# AliDualVar_B.net
KiCad netlist of a schematic drawn in EAGLE
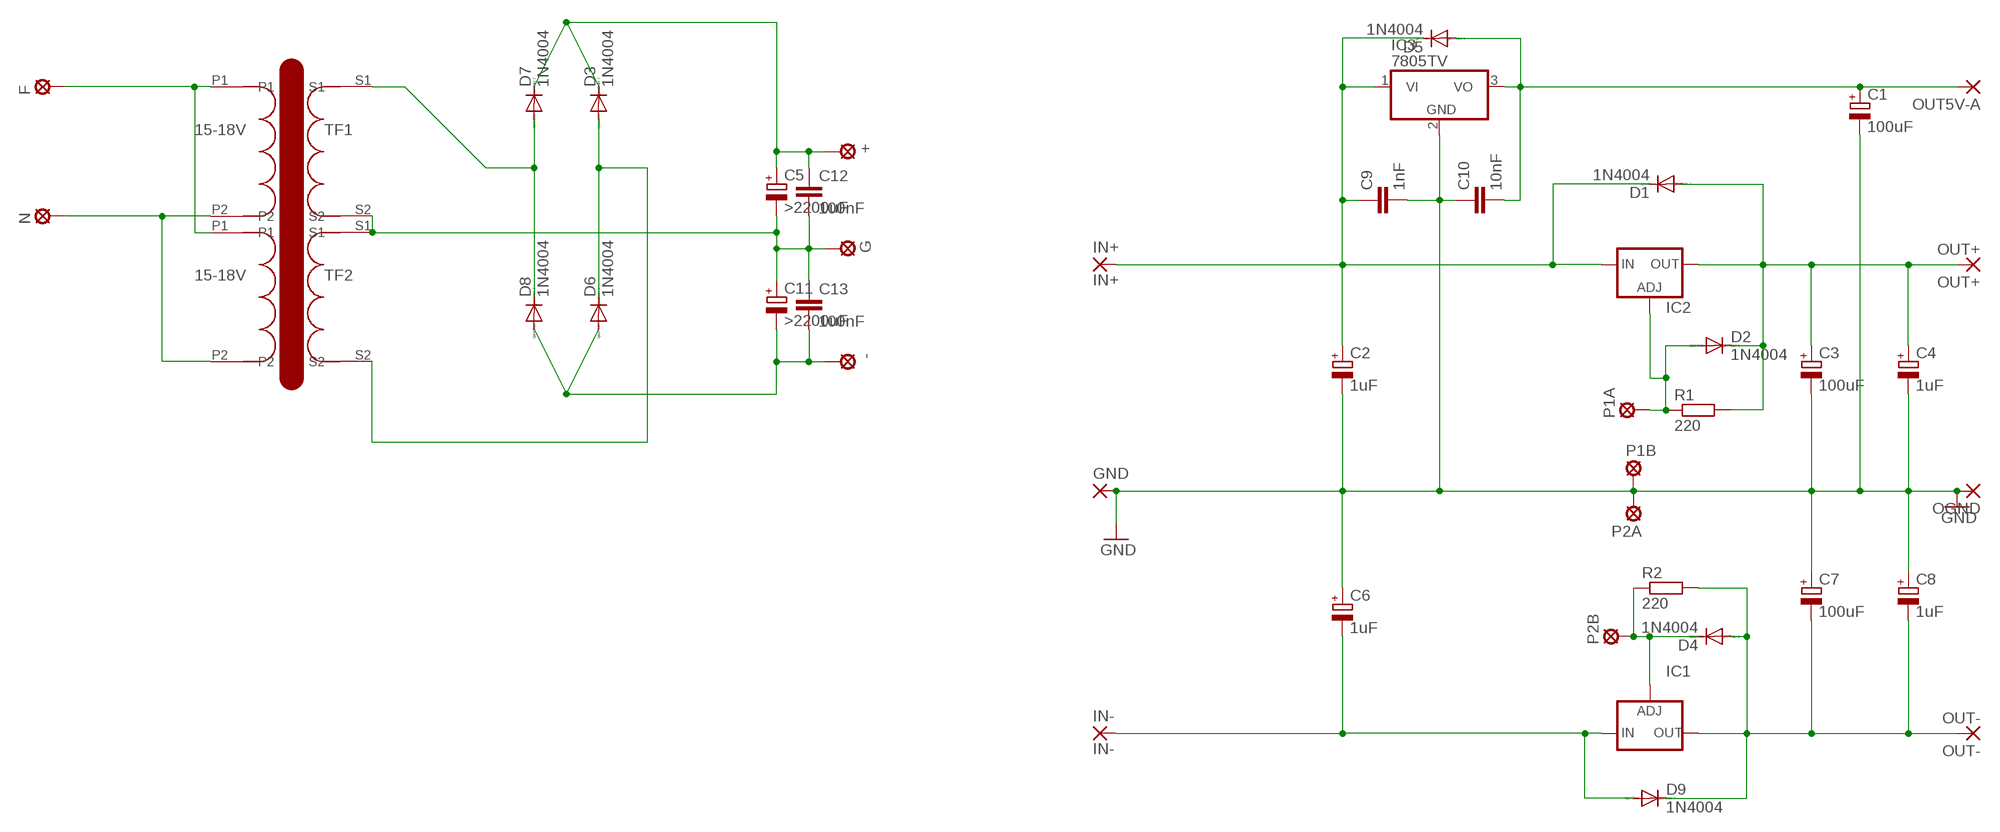
[diagram p0: schematic, sheet 1]

(export (version "E")
  (design (tool "Eeschema 10.0.6"))
  (components
    (comp (ref "+")
      (value "LSP10")
      (footprint "eagle-import:LSP10")
      (libsource (lib "eagle-import") (part "LSP10"))
    )
    (comp (ref "-")
      (value "LSP10")
      (footprint "eagle-import:LSP10")
      (libsource (lib "eagle-import") (part "LSP10"))
    )
    (comp (ref "C1")
      (value "100uF")
      (footprint "eagle-import:E5-13")
      (libsource (lib "eagle-import") (part "CPOL-EUE5-13"))
    )
    (comp (ref "C2")
      (value "1uF")
      (footprint "eagle-import:E5-13")
      (libsource (lib "eagle-import") (part "CPOL-EUE5-13"))
    )
    (comp (ref "C3")
      (value "100uF")
      (footprint "eagle-import:E5-13")
      (libsource (lib "eagle-import") (part "CPOL-EUE5-13"))
    )
    (comp (ref "C4")
      (value "1uF")
      (footprint "eagle-import:E5-13")
      (libsource (lib "eagle-import") (part "CPOL-EUE5-13"))
    )
    (comp (ref "C5")
      (value ">2200uF")
      (footprint "eagle-import:E7,5-16")
      (libsource (lib "eagle-import") (part "CPOL-EUE7.5-16"))
    )
    (comp (ref "C6")
      (value "1uF")
      (footprint "eagle-import:E5-13")
      (libsource (lib "eagle-import") (part "CPOL-EUE5-13"))
    )
    (comp (ref "C7")
      (value "100uF")
      (footprint "eagle-import:E5-13")
      (libsource (lib "eagle-import") (part "CPOL-EUE5-13"))
    )
    (comp (ref "C8")
      (value "1uF")
      (footprint "eagle-import:E5-13")
      (libsource (lib "eagle-import") (part "CPOL-EUE5-13"))
    )
    (comp (ref "C9")
      (value "1nF")
      (footprint "eagle-import:C025-024X044")
      (libsource (lib "eagle-import") (part "C-EU025-024X044"))
    )
    (comp (ref "C10")
      (value "10nF")
      (footprint "eagle-import:C025-024X044")
      (libsource (lib "eagle-import") (part "C-EU025-024X044"))
    )
    (comp (ref "C11")
      (value ">2200uF")
      (footprint "eagle-import:E7,5-16")
      (libsource (lib "eagle-import") (part "CPOL-EUE7.5-16"))
    )
    (comp (ref "C12")
      (value "100nF")
      (footprint "eagle-import:C050-035X075")
      (libsource (lib "eagle-import") (part "resistor_C-EU050-035X075"))
    )
    (comp (ref "C13")
      (value "100nF")
      (footprint "eagle-import:C050-035X075")
      (libsource (lib "eagle-import") (part "resistor_C-EU050-035X075"))
    )
    (comp (ref "D1")
      (value "1N4004")
      (footprint "eagle-import:DO41-10")
      (libsource (lib "eagle-import") (part "1N4004"))
    )
    (comp (ref "D2")
      (value "1N4004")
      (footprint "eagle-import:DO41-10")
      (libsource (lib "eagle-import") (part "1N4004"))
    )
    (comp (ref "D3")
      (value "1N4004")
      (footprint "eagle-import:DO41-10")
      (libsource (lib "eagle-import") (part "1N4004"))
    )
    (comp (ref "D4")
      (value "1N4004")
      (footprint "eagle-import:DO41-10")
      (libsource (lib "eagle-import") (part "1N4004"))
    )
    (comp (ref "D5")
      (value "1N4004")
      (footprint "eagle-import:DO41-10")
      (libsource (lib "eagle-import") (part "1N4004"))
    )
    (comp (ref "D6")
      (value "1N4004")
      (footprint "eagle-import:DO41-10")
      (libsource (lib "eagle-import") (part "1N4004"))
    )
    (comp (ref "D7")
      (value "1N4004")
      (footprint "eagle-import:DO41-10")
      (libsource (lib "eagle-import") (part "1N4004"))
    )
    (comp (ref "D8")
      (value "1N4004")
      (footprint "eagle-import:DO41-10")
      (libsource (lib "eagle-import") (part "1N4004"))
    )
    (comp (ref "D9")
      (value "1N4004")
      (footprint "eagle-import:DO41-10")
      (libsource (lib "eagle-import") (part "1N4004"))
    )
    (comp (ref "F")
      (value "LSP10")
      (footprint "eagle-import:LSP10")
      (libsource (lib "eagle-import") (part "LSP10"))
    )
    (comp (ref "G")
      (value "LSP10")
      (footprint "eagle-import:LSP10")
      (libsource (lib "eagle-import") (part "LSP10"))
    )
    (comp (ref "GND")
      (value "3,81/1,4")
      (footprint "eagle-import:3,81_1,4")
      (libsource (lib "eagle-import") (part "3,81/1,4"))
    )
    (comp (ref "IC1")
      (value "LM337TS")
      (footprint "eagle-import:337TS")
      (libsource (lib "eagle-import") (part "LM337TS"))
    )
    (comp (ref "IC2")
      (value "LM317TS")
      (footprint "eagle-import:317TS")
      (libsource (lib "eagle-import") (part "LM317TS"))
    )
    (comp (ref "IC3")
      (value "7805TV")
      (footprint "eagle-import:TO220V")
      (libsource (lib "eagle-import") (part "78TV05"))
    )
    (comp (ref "IN+")
      (value "IN+")
      (footprint "eagle-import:3,81_1,4")
      (libsource (lib "eagle-import") (part "3,81/1,4"))
    )
    (comp (ref "IN-")
      (value "IN-")
      (footprint "eagle-import:3,81_1,4")
      (libsource (lib "eagle-import") (part "3,81/1,4"))
    )
    (comp (ref "N")
      (value "LSP10")
      (footprint "eagle-import:LSP10")
      (libsource (lib "eagle-import") (part "LSP10"))
    )
    (comp (ref "OGND")
      (value "3,81/1,4")
      (footprint "eagle-import:3,81_1,4")
      (libsource (lib "eagle-import") (part "3,81/1,4"))
    )
    (comp (ref "OUT+")
      (value "OUT+")
      (footprint "eagle-import:3,81_1,4")
      (libsource (lib "eagle-import") (part "3,81/1,4"))
    )
    (comp (ref "OUT-")
      (value "OUT-")
      (footprint "eagle-import:3,81_1,4")
      (libsource (lib "eagle-import") (part "3,81/1,4"))
    )
    (comp (ref "OUT5V-A")
      (value "3,81/1,4")
      (footprint "eagle-import:3,81_1,4")
      (libsource (lib "eagle-import") (part "3,81/1,4"))
    )
    (comp (ref "P1A")
      (value "LSP10")
      (footprint "eagle-import:LSP10")
      (libsource (lib "eagle-import") (part "LSP10"))
    )
    (comp (ref "P1B")
      (value "LSP10")
      (footprint "eagle-import:LSP10")
      (libsource (lib "eagle-import") (part "LSP10"))
    )
    (comp (ref "P2A")
      (value "LSP10")
      (footprint "eagle-import:LSP10")
      (libsource (lib "eagle-import") (part "LSP10"))
    )
    (comp (ref "P2B")
      (value "LSP10")
      (footprint "eagle-import:LSP10")
      (libsource (lib "eagle-import") (part "LSP10"))
    )
    (comp (ref "R1")
      (value "220")
      (footprint "eagle-import:0207_7")
      (libsource (lib "eagle-import") (part "R-EU_0207/7"))
    )
    (comp (ref "R2")
      (value "220")
      (footprint "eagle-import:0207_7")
      (libsource (lib "eagle-import") (part "R-EU_0207/7"))
    )
    (comp (ref "TF1")
      (value "15-18V")
      (footprint "eagle-import:TRASFORMATORE_1_A")
      (libsource (lib "eagle-import") (part "TRASFORMATORE_1_A"))
    )
    (comp (ref "TF2")
      (value "15-18V")
      (footprint "eagle-import:TRASFORMATORE_1_A")
      (libsource (lib "eagle-import") (part "TRASFORMATORE_1_A"))
    )
  )
  (nets
    (net (code "1") (name "GND") (class "Default")
      (node (ref "C1") (pin "-") (pinfunction "-_-") (pintype "passive"))
      (node (ref "C10") (pin "1") (pinfunction "1_1") (pintype "passive"))
      (node (ref "C2") (pin "-") (pinfunction "-_-") (pintype "passive"))
      (node (ref "C3") (pin "-") (pinfunction "-_-") (pintype "passive"))
      (node (ref "C4") (pin "-") (pinfunction "-_-") (pintype "passive"))
      (node (ref "C6") (pin "+") (pinfunction "+_+") (pintype "passive"))
      (node (ref "C7") (pin "+") (pinfunction "+_+") (pintype "passive"))
      (node (ref "C8") (pin "+") (pinfunction "+_+") (pintype "passive"))
      (node (ref "C9") (pin "2") (pinfunction "2_2") (pintype "passive"))
      (node (ref "GND") (pin "1") (pinfunction "P_1") (pintype "passive"))
      (node (ref "IC3") (pin "2") (pinfunction "GND_2") (pintype "passive"))
      (node (ref "OGND") (pin "1") (pinfunction "P_1") (pintype "passive"))
      (node (ref "P1B") (pin "MP") (pinfunction "MP_MP") (pintype "passive"))
      (node (ref "P2A") (pin "MP") (pinfunction "MP_MP") (pintype "passive"))
    )
    (net (code "2") (name "Net-(+-PadMP)") (class "Default")
      (node (ref "+") (pin "MP") (pinfunction "MP_MP") (pintype "passive"))
      (node (ref "C12") (pin "1") (pinfunction "1_1") (pintype "passive"))
      (node (ref "C5") (pin "+") (pinfunction "+_+") (pintype "passive"))
      (node (ref "D3") (pin "C") (pinfunction "C_C") (pintype "passive"))
      (node (ref "D7") (pin "C") (pinfunction "C_C") (pintype "passive"))
    )
    (net (code "3") (name "Net-(--PadMP)") (class "Default")
      (node (ref "-") (pin "MP") (pinfunction "MP_MP") (pintype "passive"))
      (node (ref "C11") (pin "-") (pinfunction "-_-") (pintype "passive"))
      (node (ref "C13") (pin "2") (pinfunction "2_2") (pintype "passive"))
      (node (ref "D6") (pin "A") (pinfunction "A_A") (pintype "passive"))
      (node (ref "D8") (pin "A") (pinfunction "A_A") (pintype "passive"))
    )
    (net (code "4") (name "Net-(C11-Pad+)") (class "Default")
      (node (ref "C11") (pin "+") (pinfunction "+_+") (pintype "passive"))
      (node (ref "C12") (pin "2") (pinfunction "2_2") (pintype "passive"))
      (node (ref "C13") (pin "1") (pinfunction "1_1") (pintype "passive"))
      (node (ref "C5") (pin "-") (pinfunction "-_-") (pintype "passive"))
      (node (ref "G") (pin "MP") (pinfunction "MP_MP") (pintype "passive"))
      (node (ref "TF1") (pin "S2") (pinfunction "S2_S2") (pintype "bidirectional"))
      (node (ref "TF2") (pin "S1") (pinfunction "S1_S1") (pintype "bidirectional"))
    )
    (net (code "5") (name "Net-(D3-PadA)") (class "Default")
      (node (ref "D3") (pin "A") (pinfunction "A_A") (pintype "passive"))
      (node (ref "D6") (pin "C") (pinfunction "C_C") (pintype "passive"))
      (node (ref "TF2") (pin "S2") (pinfunction "S2_S2") (pintype "bidirectional"))
    )
    (net (code "6") (name "Net-(D7-PadA)") (class "Default")
      (node (ref "D7") (pin "A") (pinfunction "A_A") (pintype "passive"))
      (node (ref "D8") (pin "C") (pinfunction "C_C") (pintype "passive"))
      (node (ref "TF1") (pin "S1") (pinfunction "S1_S1") (pintype "bidirectional"))
    )
    (net (code "7") (name "Net-(F-PadMP)") (class "Default")
      (node (ref "F") (pin "MP") (pinfunction "MP_MP") (pintype "passive"))
      (node (ref "TF1") (pin "P1") (pinfunction "P1_P1") (pintype "bidirectional"))
      (node (ref "TF2") (pin "P1") (pinfunction "P1_P1") (pintype "bidirectional"))
    )
    (net (code "8") (name "Net-(IC1-ADJ)") (class "Default")
      (node (ref "D4") (pin "C") (pinfunction "C_C") (pintype "passive"))
      (node (ref "IC1") (pin "1") (pinfunction "ADJ_1") (pintype "input"))
      (node (ref "P2B") (pin "MP") (pinfunction "MP_MP") (pintype "passive"))
      (node (ref "R2") (pin "1") (pinfunction "1_1") (pintype "passive"))
    )
    (net (code "9") (name "Net-(IC1-IN)") (class "Default")
      (node (ref "C6") (pin "-") (pinfunction "-_-") (pintype "passive"))
      (node (ref "D9") (pin "A") (pinfunction "A_A") (pintype "passive"))
      (node (ref "IC1") (pin "2") (pinfunction "IN_2") (pintype "input"))
      (node (ref "IN-") (pin "1") (pinfunction "P_1") (pintype "passive"))
    )
    (net (code "10") (name "Net-(IC1-OUT)") (class "Default")
      (node (ref "C7") (pin "-") (pinfunction "-_-") (pintype "passive"))
      (node (ref "C8") (pin "-") (pinfunction "-_-") (pintype "passive"))
      (node (ref "D4") (pin "A") (pinfunction "A_A") (pintype "passive"))
      (node (ref "D9") (pin "C") (pinfunction "C_C") (pintype "passive"))
      (node (ref "IC1") (pin "3") (pinfunction "OUT_3") (pintype "passive"))
      (node (ref "OUT-") (pin "1") (pinfunction "P_1") (pintype "passive"))
      (node (ref "R2") (pin "2") (pinfunction "2_2") (pintype "passive"))
    )
    (net (code "11") (name "Net-(IC2-ADJ)") (class "Default")
      (node (ref "D2") (pin "A") (pinfunction "A_A") (pintype "passive"))
      (node (ref "IC2") (pin "1") (pinfunction "ADJ_1") (pintype "input"))
      (node (ref "P1A") (pin "MP") (pinfunction "MP_MP") (pintype "passive"))
      (node (ref "R1") (pin "1") (pinfunction "1_1") (pintype "passive"))
    )
    (net (code "12") (name "Net-(IC2-IN)") (class "Default")
      (node (ref "C2") (pin "+") (pinfunction "+_+") (pintype "passive"))
      (node (ref "C9") (pin "1") (pinfunction "1_1") (pintype "passive"))
      (node (ref "D1") (pin "C") (pinfunction "C_C") (pintype "passive"))
      (node (ref "D5") (pin "C") (pinfunction "C_C") (pintype "passive"))
      (node (ref "IC2") (pin "3") (pinfunction "IN_3") (pintype "input"))
      (node (ref "IC3") (pin "1") (pinfunction "VI_1") (pintype "input"))
      (node (ref "IN+") (pin "1") (pinfunction "P_1") (pintype "passive"))
    )
    (net (code "13") (name "Net-(IC2-OUT)") (class "Default")
      (node (ref "C3") (pin "+") (pinfunction "+_+") (pintype "passive"))
      (node (ref "C4") (pin "+") (pinfunction "+_+") (pintype "passive"))
      (node (ref "D1") (pin "A") (pinfunction "A_A") (pintype "passive"))
      (node (ref "D2") (pin "C") (pinfunction "C_C") (pintype "passive"))
      (node (ref "IC2") (pin "2") (pinfunction "OUT_2") (pintype "passive"))
      (node (ref "OUT+") (pin "1") (pinfunction "P_1") (pintype "passive"))
      (node (ref "R1") (pin "2") (pinfunction "2_2") (pintype "passive"))
    )
    (net (code "14") (name "Net-(IC3-VO)") (class "Default")
      (node (ref "C1") (pin "+") (pinfunction "+_+") (pintype "passive"))
      (node (ref "C10") (pin "2") (pinfunction "2_2") (pintype "passive"))
      (node (ref "D5") (pin "A") (pinfunction "A_A") (pintype "passive"))
      (node (ref "IC3") (pin "3") (pinfunction "VO_3") (pintype "passive"))
      (node (ref "OUT5V-A") (pin "1") (pinfunction "P_1") (pintype "passive"))
    )
    (net (code "15") (name "Net-(N-PadMP)") (class "Default")
      (node (ref "N") (pin "MP") (pinfunction "MP_MP") (pintype "passive"))
      (node (ref "TF1") (pin "P2") (pinfunction "P2_P2") (pintype "bidirectional"))
      (node (ref "TF2") (pin "P2") (pinfunction "P2_P2") (pintype "bidirectional"))
    )
  )
)
